# Connector_0.net
KiCad netlist of a schematic drawn in Altium Designer
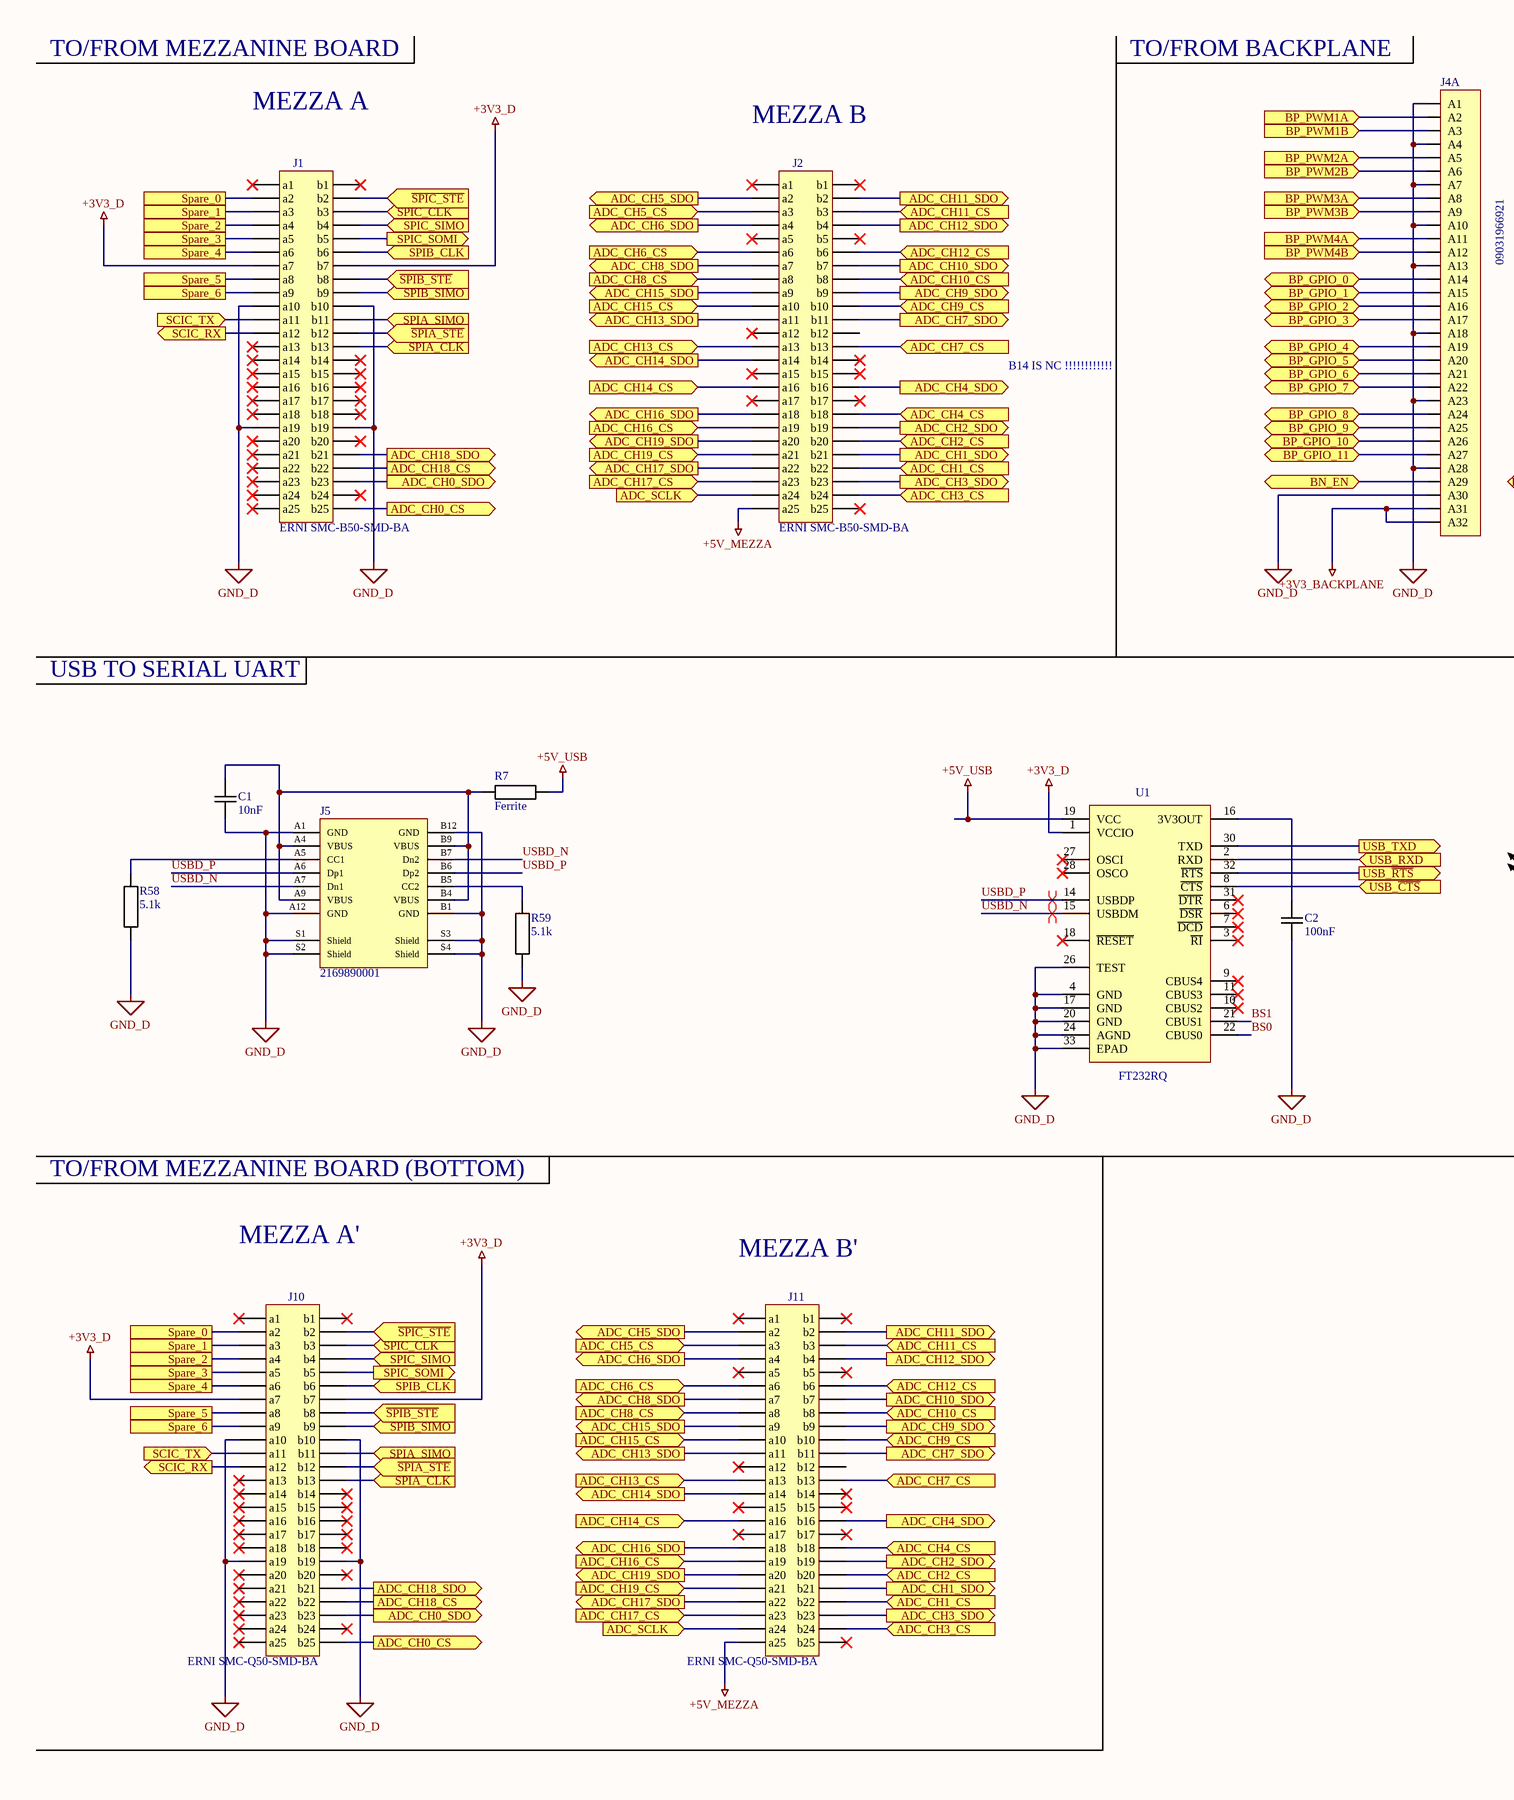
[diagram p0: Connector_0.SchDoc, left]
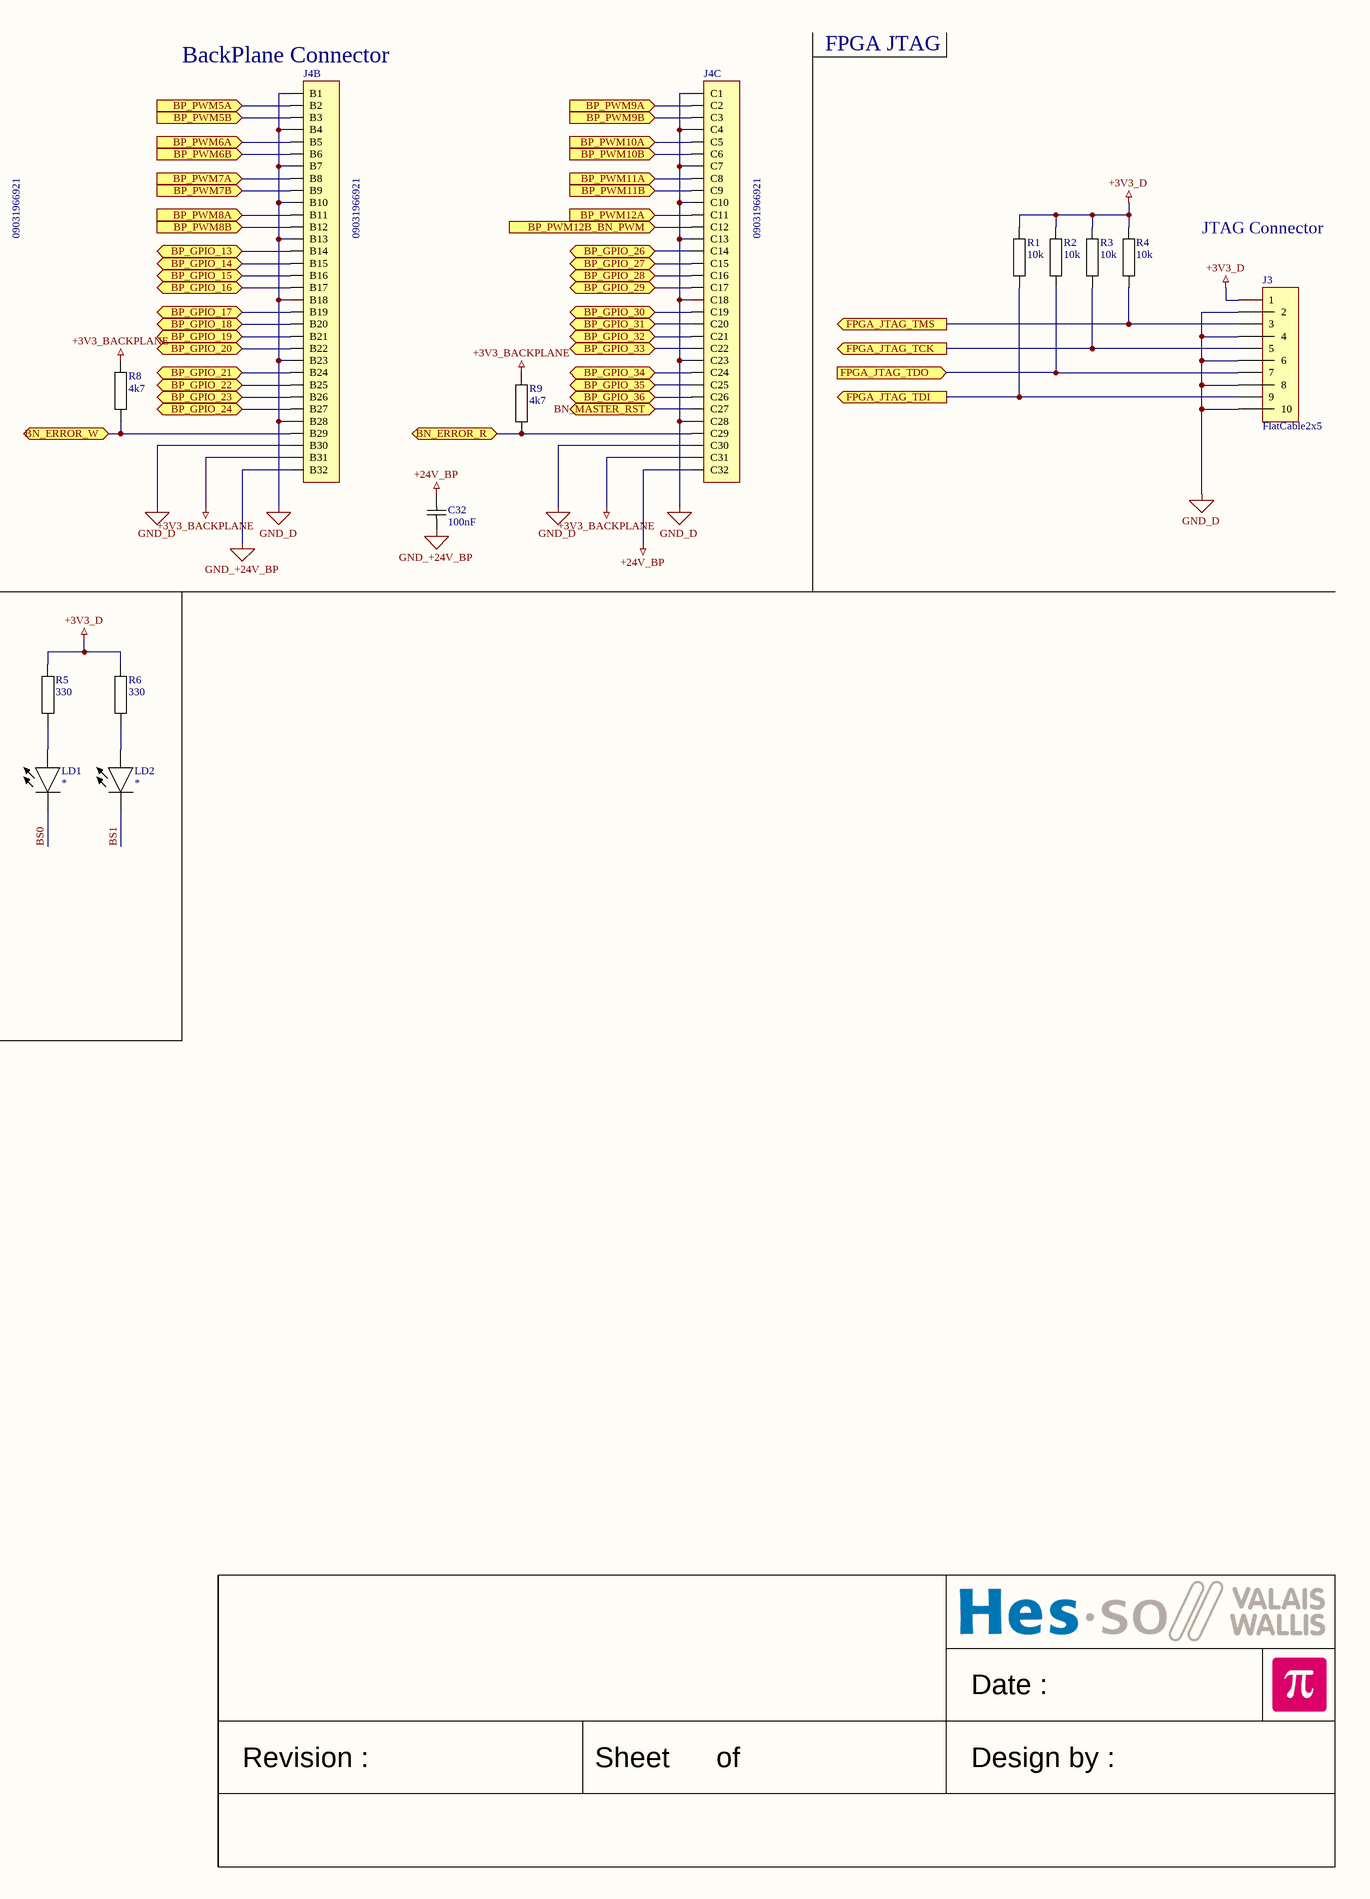
[diagram p1: Connector_0.SchDoc, right]

(export (version "E")
  (design (tool "Eeschema 10.0.6"))
  (components
    (comp (ref "C1")
      (value "10nF")
      (footprint "CAPACITOR 1608 REFLOW")
      (description "Capacitor X7R 10% 50V 1608(0603)")
      (libsource (lib "Capacitor") (part "Capacitor"))
    )
    (comp (ref "C2")
      (value "100nF")
      (footprint "CAPACITOR 1608 REFLOW")
      (description "Capacitor X7R 10% 50V 1608(0603)")
      (libsource (lib "Capacitor") (part "Capacitor"))
    )
    (comp (ref "C32")
      (value "100nF")
      (footprint "CAPACITOR 1608 REFLOW")
      (description "Capacitor X7R 10% 50V 1608(0603)")
      (libsource (lib "Capacitor") (part "Capacitor"))
    )
    (comp (ref "J1")
      (value "ERNI SMC-B50-SMD-BA")
      (footprint "ERNI SMC-B50-SMD-BA")
      (description "Female 1.27 pitch 2x25 pin connector")
      (libsource (lib "Connector") (part "ERNI SMC-B50-SMD-BA"))
    )
    (comp (ref "J2")
      (value "ERNI SMC-B50-SMD-BA")
      (footprint "ERNI SMC-B50-SMD-BA")
      (description "Female 1.27 pitch 2x25 pin connector")
      (libsource (lib "Connector") (part "ERNI SMC-B50-SMD-BA"))
    )
    (comp (ref "J3")
      (value "FlatCable2x5")
      (footprint "FlatCable2x5 2MM Right Angle TH FCI 98614-G61-10ULF")
      (libsource (lib "Connector") (part "FlatCable2x5"))
    )
    (comp (ref "J4")
      (value "09031966921")
      (footprint "DIN41612 MALE 3X32 ABC R90")
      (description "DIN41612 MALE 3X32 ABC R90")
      (fields (field (name "MANUFACTURER") "Harting"))
      (libsource (lib "Connector") (part "DIN41612 MALE 3X32 ABC R90"))
    )
    (comp (ref "J5")
      (value "2169890001")
      (footprint "USB-C-TH MOLEX 2169890001")
      (description "USB-C Receptacle Connector 24 Position Through Hole, Right Angle")
      (libsource (lib "Connector") (part "USB-C-Molex 2169890001"))
    )
    (comp (ref "J10")
      (value "ERNI SMC-Q50-SMD-BA")
      (footprint "ERNI SMC-Q50-SMD-BA")
      (description "Male 1.27 pitch 2x25 pin connector")
      (libsource (lib "Connector") (part "ERNI SMC-Q50-SMD-BA"))
    )
    (comp (ref "J11")
      (value "ERNI SMC-Q50-SMD-BA")
      (footprint "ERNI SMC-Q50-SMD-BA")
      (description "Male 1.27 pitch 2x25 pin connector")
      (libsource (lib "Connector") (part "ERNI SMC-Q50-SMD-BA"))
    )
    (comp (ref "LD1")
      (value "*")
      (footprint "LED 1608 REFLOW")
      (description "LED generic")
      (libsource (lib "Diode") (part "LED"))
    )
    (comp (ref "LD2")
      (value "*")
      (footprint "LED 1608 REFLOW")
      (description "LED generic")
      (libsource (lib "Diode") (part "LED"))
    )
    (comp (ref "R1")
      (value "10k")
      (footprint "RESISTOR 1608 REFLOW")
      (description "Resistor 1% 50V 100mW 1608(0603)")
      (libsource (lib "Resistor") (part "Resistor"))
    )
    (comp (ref "R2")
      (value "10k")
      (footprint "RESISTOR 1608 REFLOW")
      (description "Resistor 1% 50V 100mW 1608(0603)")
      (libsource (lib "Resistor") (part "Resistor"))
    )
    (comp (ref "R3")
      (value "10k")
      (footprint "RESISTOR 1608 REFLOW")
      (description "Resistor 1% 50V 100mW 1608(0603)")
      (libsource (lib "Resistor") (part "Resistor"))
    )
    (comp (ref "R4")
      (value "10k")
      (footprint "RESISTOR 1608 REFLOW")
      (description "Resistor 1% 50V 100mW 1608(0603)")
      (libsource (lib "Resistor") (part "Resistor"))
    )
    (comp (ref "R5")
      (value "330")
      (footprint "RESISTOR 2012 REFLOW")
      (description "Resistor 1% 50V 125mW 2012(0805)")
      (libsource (lib "Resistor") (part "Resistor"))
    )
    (comp (ref "R6")
      (value "330")
      (footprint "RESISTOR 2012 REFLOW")
      (description "Resistor 1% 50V 125mW 2012(0805)")
      (libsource (lib "Resistor") (part "Resistor"))
    )
    (comp (ref "R7")
      (value "Ferrite")
      (footprint "RESISTOR 1608 REFLOW")
      (description "Resistor 1% 50V 100mW 1608(0603)")
      (libsource (lib "Resistor") (part "Resistor"))
    )
    (comp (ref "R8")
      (value "4k7")
      (footprint "RESISTOR 1608 REFLOW")
      (description "Resistor 1% 50V 100mW 1608(0603)")
      (libsource (lib "Resistor") (part "Resistor"))
    )
    (comp (ref "R9")
      (value "4k7")
      (footprint "RESISTOR 1608 REFLOW")
      (description "Resistor 1% 50V 100mW 1608(0603)")
      (libsource (lib "Resistor") (part "Resistor"))
    )
    (comp (ref "R58")
      (value "5.1k")
      (footprint "RESISTOR 1608 REFLOW")
      (description "Resistor 1% 50V 100mW 1608(0603)")
      (libsource (lib "Resistor") (part "Resistor"))
    )
    (comp (ref "R59")
      (value "5.1k")
      (footprint "RESISTOR 1608 REFLOW")
      (description "Resistor 1% 50V 100mW 1608(0603)")
      (libsource (lib "Resistor") (part "Resistor"))
    )
    (comp (ref "U1")
      (value "FT232RQ")
      (footprint "QFN32 P0.5 T3.2x3.2 C5.0X5.0 H1.0")
      (description "24-Bit ADC with Ultra Low Noise PGIA - Crystal")
      (libsource (lib "IntegratedCircuit - Copy") (part "FT232RQ"))
    )
  )
  (nets
    (net (code "1") (name "+3V3_BACKPLANE") (class "Default")
      (node (ref "J4") (pin "A31") (pinfunction "A31_A31") (pintype "passive"))
      (node (ref "J4") (pin "A32") (pinfunction "A32_A32") (pintype "passive"))
      (node (ref "J4") (pin "B31") (pinfunction "B31_B31") (pintype "passive"))
      (node (ref "J4") (pin "C31") (pinfunction "C31_C31") (pintype "passive"))
      (node (ref "R8") (pin "2") (pinfunction "2_2") (pintype "passive"))
      (node (ref "R9") (pin "2") (pinfunction "2_2") (pintype "passive"))
    )
    (net (code "2") (name "+3V3_D") (class "Default")
      (node (ref "J1") (pin "a7") (pinfunction "a7_a7") (pintype "passive"))
      (node (ref "J1") (pin "b7") (pinfunction "b7_b7") (pintype "passive"))
      (node (ref "J10") (pin "a7") (pinfunction "a7_a7") (pintype "passive"))
      (node (ref "J10") (pin "b7") (pinfunction "b7_b7") (pintype "passive"))
      (node (ref "J3") (pin "1") (pinfunction "1_1") (pintype "passive"))
      (node (ref "R1") (pin "2") (pinfunction "2_2") (pintype "passive"))
      (node (ref "R2") (pin "2") (pinfunction "2_2") (pintype "passive"))
      (node (ref "R3") (pin "2") (pinfunction "2_2") (pintype "passive"))
      (node (ref "R4") (pin "2") (pinfunction "2_2") (pintype "passive"))
      (node (ref "R5") (pin "2") (pinfunction "2_2") (pintype "passive"))
      (node (ref "R6") (pin "2") (pinfunction "2_2") (pintype "passive"))
      (node (ref "U1") (pin "1") (pinfunction "VCCIO_1") (pintype "passive"))
    )
    (net (code "3") (name "+5V_MEZZA") (class "Default")
      (node (ref "J11") (pin "a25") (pinfunction "a25_a25") (pintype "passive"))
      (node (ref "J2") (pin "a25") (pinfunction "a25_a25") (pintype "passive"))
    )
    (net (code "4") (name "+5V_USB") (class "Default")
      (node (ref "R7") (pin "2") (pinfunction "2_2") (pintype "passive"))
      (node (ref "U1") (pin "19") (pinfunction "VCC_19") (pintype "passive"))
    )
    (net (code "5") (name "+24V_BP") (class "Default")
      (node (ref "C32") (pin "2") (pinfunction "2_2") (pintype "passive"))
      (node (ref "J4") (pin "C32") (pinfunction "C32_C32") (pintype "passive"))
    )
    (net (code "6") (name "/ADC_CH0_CS") (class "Default")
      (node (ref "J1") (pin "b25") (pinfunction "b25_b25") (pintype "passive"))
      (node (ref "J10") (pin "b25") (pinfunction "b25_b25") (pintype "passive"))
    )
    (net (code "7") (name "/ADC_CH0_SDO") (class "Default")
      (node (ref "J1") (pin "b23") (pinfunction "b23_b23") (pintype "passive"))
      (node (ref "J10") (pin "b23") (pinfunction "b23_b23") (pintype "passive"))
    )
    (net (code "8") (name "/ADC_CH1_CS") (class "Default")
      (node (ref "J11") (pin "b22") (pinfunction "b22_b22") (pintype "passive"))
      (node (ref "J2") (pin "b22") (pinfunction "b22_b22") (pintype "passive"))
    )
    (net (code "9") (name "/ADC_CH1_SDO") (class "Default")
      (node (ref "J11") (pin "b21") (pinfunction "b21_b21") (pintype "passive"))
      (node (ref "J2") (pin "b21") (pinfunction "b21_b21") (pintype "passive"))
    )
    (net (code "10") (name "/ADC_CH2_CS") (class "Default")
      (node (ref "J11") (pin "b20") (pinfunction "b20_b20") (pintype "passive"))
      (node (ref "J2") (pin "b20") (pinfunction "b20_b20") (pintype "passive"))
    )
    (net (code "11") (name "/ADC_CH2_SDO") (class "Default")
      (node (ref "J11") (pin "b19") (pinfunction "b19_b19") (pintype "passive"))
      (node (ref "J2") (pin "b19") (pinfunction "b19_b19") (pintype "passive"))
    )
    (net (code "12") (name "/ADC_CH3_CS") (class "Default")
      (node (ref "J11") (pin "b24") (pinfunction "b24_b24") (pintype "passive"))
      (node (ref "J2") (pin "b24") (pinfunction "b24_b24") (pintype "passive"))
    )
    (net (code "13") (name "/ADC_CH3_SDO") (class "Default")
      (node (ref "J11") (pin "b23") (pinfunction "b23_b23") (pintype "passive"))
      (node (ref "J2") (pin "b23") (pinfunction "b23_b23") (pintype "passive"))
    )
    (net (code "14") (name "/ADC_CH4_CS") (class "Default")
      (node (ref "J11") (pin "b18") (pinfunction "b18_b18") (pintype "passive"))
      (node (ref "J2") (pin "b18") (pinfunction "b18_b18") (pintype "passive"))
    )
    (net (code "15") (name "/ADC_CH4_SDO") (class "Default")
      (node (ref "J11") (pin "b16") (pinfunction "b16_b16") (pintype "passive"))
      (node (ref "J2") (pin "b16") (pinfunction "b16_b16") (pintype "passive"))
    )
    (net (code "16") (name "/ADC_CH5_CS") (class "Default")
      (node (ref "J11") (pin "a3") (pinfunction "a3_a3") (pintype "passive"))
      (node (ref "J2") (pin "a3") (pinfunction "a3_a3") (pintype "passive"))
    )
    (net (code "17") (name "/ADC_CH5_SDO") (class "Default")
      (node (ref "J11") (pin "a2") (pinfunction "a2_a2") (pintype "passive"))
      (node (ref "J2") (pin "a2") (pinfunction "a2_a2") (pintype "passive"))
    )
    (net (code "18") (name "/ADC_CH6_CS") (class "Default")
      (node (ref "J11") (pin "a6") (pinfunction "a6_a6") (pintype "passive"))
      (node (ref "J2") (pin "a6") (pinfunction "a6_a6") (pintype "passive"))
    )
    (net (code "19") (name "/ADC_CH6_SDO") (class "Default")
      (node (ref "J11") (pin "a4") (pinfunction "a4_a4") (pintype "passive"))
      (node (ref "J2") (pin "a4") (pinfunction "a4_a4") (pintype "passive"))
    )
    (net (code "20") (name "/ADC_CH7_CS") (class "Default")
      (node (ref "J11") (pin "b13") (pinfunction "b13_b13") (pintype "passive"))
      (node (ref "J2") (pin "b13") (pinfunction "b13_b13") (pintype "passive"))
    )
    (net (code "21") (name "/ADC_CH7_SDO") (class "Default")
      (node (ref "J11") (pin "b11") (pinfunction "b11_b11") (pintype "passive"))
      (node (ref "J2") (pin "b11") (pinfunction "b11_b11") (pintype "passive"))
    )
    (net (code "22") (name "/ADC_CH8_CS") (class "Default")
      (node (ref "J11") (pin "a8") (pinfunction "a8_a8") (pintype "passive"))
      (node (ref "J2") (pin "a8") (pinfunction "a8_a8") (pintype "passive"))
    )
    (net (code "23") (name "/ADC_CH8_SDO") (class "Default")
      (node (ref "J11") (pin "a7") (pinfunction "a7_a7") (pintype "passive"))
      (node (ref "J2") (pin "a7") (pinfunction "a7_a7") (pintype "passive"))
    )
    (net (code "24") (name "/ADC_CH9_CS") (class "Default")
      (node (ref "J11") (pin "b10") (pinfunction "b10_b10") (pintype "passive"))
      (node (ref "J2") (pin "b10") (pinfunction "b10_b10") (pintype "passive"))
    )
    (net (code "25") (name "/ADC_CH9_SDO") (class "Default")
      (node (ref "J11") (pin "b9") (pinfunction "b9_b9") (pintype "passive"))
      (node (ref "J2") (pin "b9") (pinfunction "b9_b9") (pintype "passive"))
    )
    (net (code "26") (name "/ADC_CH10_CS") (class "Default")
      (node (ref "J11") (pin "b8") (pinfunction "b8_b8") (pintype "passive"))
      (node (ref "J2") (pin "b8") (pinfunction "b8_b8") (pintype "passive"))
    )
    (net (code "27") (name "/ADC_CH10_SDO") (class "Default")
      (node (ref "J11") (pin "b7") (pinfunction "b7_b7") (pintype "passive"))
      (node (ref "J2") (pin "b7") (pinfunction "b7_b7") (pintype "passive"))
    )
    (net (code "28") (name "/ADC_CH11_CS") (class "Default")
      (node (ref "J11") (pin "b3") (pinfunction "b3_b3") (pintype "passive"))
      (node (ref "J2") (pin "b3") (pinfunction "b3_b3") (pintype "passive"))
    )
    (net (code "29") (name "/ADC_CH11_SDO") (class "Default")
      (node (ref "J11") (pin "b2") (pinfunction "b2_b2") (pintype "passive"))
      (node (ref "J2") (pin "b2") (pinfunction "b2_b2") (pintype "passive"))
    )
    (net (code "30") (name "/ADC_CH12_CS") (class "Default")
      (node (ref "J11") (pin "b6") (pinfunction "b6_b6") (pintype "passive"))
      (node (ref "J2") (pin "b6") (pinfunction "b6_b6") (pintype "passive"))
    )
    (net (code "31") (name "/ADC_CH12_SDO") (class "Default")
      (node (ref "J11") (pin "b4") (pinfunction "b4_b4") (pintype "passive"))
      (node (ref "J2") (pin "b4") (pinfunction "b4_b4") (pintype "passive"))
    )
    (net (code "32") (name "/ADC_CH13_CS") (class "Default")
      (node (ref "J11") (pin "a13") (pinfunction "a13_a13") (pintype "passive"))
      (node (ref "J2") (pin "a13") (pinfunction "a13_a13") (pintype "passive"))
    )
    (net (code "33") (name "/ADC_CH13_SDO") (class "Default")
      (node (ref "J11") (pin "a11") (pinfunction "a11_a11") (pintype "passive"))
      (node (ref "J2") (pin "a11") (pinfunction "a11_a11") (pintype "passive"))
    )
    (net (code "34") (name "/ADC_CH14_CS") (class "Default")
      (node (ref "J11") (pin "a16") (pinfunction "a16_a16") (pintype "passive"))
      (node (ref "J2") (pin "a16") (pinfunction "a16_a16") (pintype "passive"))
    )
    (net (code "35") (name "/ADC_CH14_SDO") (class "Default")
      (node (ref "J11") (pin "a14") (pinfunction "a14_a14") (pintype "passive"))
      (node (ref "J2") (pin "a14") (pinfunction "a14_a14") (pintype "passive"))
    )
    (net (code "36") (name "/ADC_CH15_CS") (class "Default")
      (node (ref "J11") (pin "a10") (pinfunction "a10_a10") (pintype "passive"))
      (node (ref "J2") (pin "a10") (pinfunction "a10_a10") (pintype "passive"))
    )
    (net (code "37") (name "/ADC_CH15_SDO") (class "Default")
      (node (ref "J11") (pin "a9") (pinfunction "a9_a9") (pintype "passive"))
      (node (ref "J2") (pin "a9") (pinfunction "a9_a9") (pintype "passive"))
    )
    (net (code "38") (name "/ADC_CH16_CS") (class "Default")
      (node (ref "J11") (pin "a19") (pinfunction "a19_a19") (pintype "passive"))
      (node (ref "J2") (pin "a19") (pinfunction "a19_a19") (pintype "passive"))
    )
    (net (code "39") (name "/ADC_CH16_SDO") (class "Default")
      (node (ref "J11") (pin "a18") (pinfunction "a18_a18") (pintype "passive"))
      (node (ref "J2") (pin "a18") (pinfunction "a18_a18") (pintype "passive"))
    )
    (net (code "40") (name "/ADC_CH17_CS") (class "Default")
      (node (ref "J11") (pin "a23") (pinfunction "a23_a23") (pintype "passive"))
      (node (ref "J2") (pin "a23") (pinfunction "a23_a23") (pintype "passive"))
    )
    (net (code "41") (name "/ADC_CH17_SDO") (class "Default")
      (node (ref "J11") (pin "a22") (pinfunction "a22_a22") (pintype "passive"))
      (node (ref "J2") (pin "a22") (pinfunction "a22_a22") (pintype "passive"))
    )
    (net (code "42") (name "/ADC_CH18_CS") (class "Default")
      (node (ref "J1") (pin "b22") (pinfunction "b22_b22") (pintype "passive"))
      (node (ref "J10") (pin "b22") (pinfunction "b22_b22") (pintype "passive"))
    )
    (net (code "43") (name "/ADC_CH18_SDO") (class "Default")
      (node (ref "J1") (pin "b21") (pinfunction "b21_b21") (pintype "passive"))
      (node (ref "J10") (pin "b21") (pinfunction "b21_b21") (pintype "passive"))
    )
    (net (code "44") (name "/ADC_CH19_CS") (class "Default")
      (node (ref "J11") (pin "a21") (pinfunction "a21_a21") (pintype "passive"))
      (node (ref "J2") (pin "a21") (pinfunction "a21_a21") (pintype "passive"))
    )
    (net (code "45") (name "/ADC_CH19_SDO") (class "Default")
      (node (ref "J11") (pin "a20") (pinfunction "a20_a20") (pintype "passive"))
      (node (ref "J2") (pin "a20") (pinfunction "a20_a20") (pintype "passive"))
    )
    (net (code "46") (name "/ADC_SCLK") (class "Default")
      (node (ref "J11") (pin "a24") (pinfunction "a24_a24") (pintype "passive"))
      (node (ref "J2") (pin "a24") (pinfunction "a24_a24") (pintype "passive"))
    )
    (net (code "47") (name "/BN_EN") (class "Default")
      (node (ref "J4") (pin "A29") (pinfunction "A29_A29") (pintype "passive"))
    )
    (net (code "48") (name "/BN_ERROR_R") (class "Default")
      (node (ref "J4") (pin "C29") (pinfunction "C29_C29") (pintype "passive"))
      (node (ref "R9") (pin "1") (pinfunction "1_1") (pintype "passive"))
    )
    (net (code "49") (name "/BN_ERROR_W") (class "Default")
      (node (ref "J4") (pin "B29") (pinfunction "B29_B29") (pintype "passive"))
      (node (ref "R8") (pin "1") (pinfunction "1_1") (pintype "passive"))
    )
    (net (code "50") (name "/BN_MASTER_RST") (class "Default")
      (node (ref "J4") (pin "C27") (pinfunction "C27_C27") (pintype "passive"))
    )
    (net (code "51") (name "/BP_GPIO_0") (class "Default")
      (node (ref "J4") (pin "A14") (pinfunction "A14_A14") (pintype "passive"))
    )
    (net (code "52") (name "/BP_GPIO_1") (class "Default")
      (node (ref "J4") (pin "A15") (pinfunction "A15_A15") (pintype "passive"))
    )
    (net (code "53") (name "/BP_GPIO_2") (class "Default")
      (node (ref "J4") (pin "A16") (pinfunction "A16_A16") (pintype "passive"))
    )
    (net (code "54") (name "/BP_GPIO_3") (class "Default")
      (node (ref "J4") (pin "A17") (pinfunction "A17_A17") (pintype "passive"))
    )
    (net (code "55") (name "/BP_GPIO_4") (class "Default")
      (node (ref "J4") (pin "A19") (pinfunction "A19_A19") (pintype "passive"))
    )
    (net (code "56") (name "/BP_GPIO_5") (class "Default")
      (node (ref "J4") (pin "A20") (pinfunction "A20_A20") (pintype "passive"))
    )
    (net (code "57") (name "/BP_GPIO_6") (class "Default")
      (node (ref "J4") (pin "A21") (pinfunction "A21_A21") (pintype "passive"))
    )
    (net (code "58") (name "/BP_GPIO_7") (class "Default")
      (node (ref "J4") (pin "A22") (pinfunction "A22_A22") (pintype "passive"))
    )
    (net (code "59") (name "/BP_GPIO_8") (class "Default")
      (node (ref "J4") (pin "A24") (pinfunction "A24_A24") (pintype "passive"))
    )
    (net (code "60") (name "/BP_GPIO_9") (class "Default")
      (node (ref "J4") (pin "A25") (pinfunction "A25_A25") (pintype "passive"))
    )
    (net (code "61") (name "/BP_GPIO_10") (class "Default")
      (node (ref "J4") (pin "A26") (pinfunction "A26_A26") (pintype "passive"))
    )
    (net (code "62") (name "/BP_GPIO_11") (class "Default")
      (node (ref "J4") (pin "A27") (pinfunction "A27_A27") (pintype "passive"))
    )
    (net (code "63") (name "/BP_GPIO_13") (class "Default")
      (node (ref "J4") (pin "B14") (pinfunction "B14_B14") (pintype "passive"))
    )
    (net (code "64") (name "/BP_GPIO_14") (class "Default")
      (node (ref "J4") (pin "B15") (pinfunction "B15_B15") (pintype "passive"))
    )
    (net (code "65") (name "/BP_GPIO_15") (class "Default")
      (node (ref "J4") (pin "B16") (pinfunction "B16_B16") (pintype "passive"))
    )
    (net (code "66") (name "/BP_GPIO_16") (class "Default")
      (node (ref "J4") (pin "B17") (pinfunction "B17_B17") (pintype "passive"))
    )
    (net (code "67") (name "/BP_GPIO_17") (class "Default")
      (node (ref "J4") (pin "B19") (pinfunction "B19_B19") (pintype "passive"))
    )
    (net (code "68") (name "/BP_GPIO_18") (class "Default")
      (node (ref "J4") (pin "B20") (pinfunction "B20_B20") (pintype "passive"))
    )
    (net (code "69") (name "/BP_GPIO_19") (class "Default")
      (node (ref "J4") (pin "B21") (pinfunction "B21_B21") (pintype "passive"))
    )
    (net (code "70") (name "/BP_GPIO_20") (class "Default")
      (node (ref "J4") (pin "B22") (pinfunction "B22_B22") (pintype "passive"))
    )
    (net (code "71") (name "/BP_GPIO_21") (class "Default")
      (node (ref "J4") (pin "B24") (pinfunction "B24_B24") (pintype "passive"))
    )
    (net (code "72") (name "/BP_GPIO_22") (class "Default")
      (node (ref "J4") (pin "B25") (pinfunction "B25_B25") (pintype "passive"))
    )
    (net (code "73") (name "/BP_GPIO_23") (class "Default")
      (node (ref "J4") (pin "B26") (pinfunction "B26_B26") (pintype "passive"))
    )
    (net (code "74") (name "/BP_GPIO_24") (class "Default")
      (node (ref "J4") (pin "B27") (pinfunction "B27_B27") (pintype "passive"))
    )
    (net (code "75") (name "/BP_GPIO_26") (class "Default")
      (node (ref "J4") (pin "C14") (pinfunction "C14_C14") (pintype "passive"))
    )
    (net (code "76") (name "/BP_GPIO_27") (class "Default")
      (node (ref "J4") (pin "C15") (pinfunction "C15_C15") (pintype "passive"))
    )
    (net (code "77") (name "/BP_GPIO_28") (class "Default")
      (node (ref "J4") (pin "C16") (pinfunction "C16_C16") (pintype "passive"))
    )
    (net (code "78") (name "/BP_GPIO_29") (class "Default")
      (node (ref "J4") (pin "C17") (pinfunction "C17_C17") (pintype "passive"))
    )
    (net (code "79") (name "/BP_GPIO_30") (class "Default")
      (node (ref "J4") (pin "C19") (pinfunction "C19_C19") (pintype "passive"))
    )
    (net (code "80") (name "/BP_GPIO_31") (class "Default")
      (node (ref "J4") (pin "C20") (pinfunction "C20_C20") (pintype "passive"))
    )
    (net (code "81") (name "/BP_GPIO_32") (class "Default")
      (node (ref "J4") (pin "C21") (pinfunction "C21_C21") (pintype "passive"))
    )
    (net (code "82") (name "/BP_GPIO_33") (class "Default")
      (node (ref "J4") (pin "C22") (pinfunction "C22_C22") (pintype "passive"))
    )
    (net (code "83") (name "/BP_GPIO_34") (class "Default")
      (node (ref "J4") (pin "C24") (pinfunction "C24_C24") (pintype "passive"))
    )
    (net (code "84") (name "/BP_GPIO_35") (class "Default")
      (node (ref "J4") (pin "C25") (pinfunction "C25_C25") (pintype "passive"))
    )
    (net (code "85") (name "/BP_GPIO_36") (class "Default")
      (node (ref "J4") (pin "C26") (pinfunction "C26_C26") (pintype "passive"))
    )
    (net (code "86") (name "/BP_PWM1A") (class "Default")
      (node (ref "J4") (pin "A2") (pinfunction "A2_A2") (pintype "passive"))
    )
    (net (code "87") (name "/BP_PWM1B") (class "Default")
      (node (ref "J4") (pin "A3") (pinfunction "A3_A3") (pintype "passive"))
    )
    (net (code "88") (name "/BP_PWM2A") (class "Default")
      (node (ref "J4") (pin "A5") (pinfunction "A5_A5") (pintype "passive"))
    )
    (net (code "89") (name "/BP_PWM2B") (class "Default")
      (node (ref "J4") (pin "A6") (pinfunction "A6_A6") (pintype "passive"))
    )
    (net (code "90") (name "/BP_PWM3A") (class "Default")
      (node (ref "J4") (pin "A8") (pinfunction "A8_A8") (pintype "passive"))
    )
    (net (code "91") (name "/BP_PWM3B") (class "Default")
      (node (ref "J4") (pin "A9") (pinfunction "A9_A9") (pintype "passive"))
    )
    (net (code "92") (name "/BP_PWM4A") (class "Default")
      (node (ref "J4") (pin "A11") (pinfunction "A11_A11") (pintype "passive"))
    )
    (net (code "93") (name "/BP_PWM4B") (class "Default")
      (node (ref "J4") (pin "A12") (pinfunction "A12_A12") (pintype "passive"))
    )
    (net (code "94") (name "/BP_PWM5A") (class "Default")
      (node (ref "J4") (pin "B2") (pinfunction "B2_B2") (pintype "passive"))
    )
    (net (code "95") (name "/BP_PWM5B") (class "Default")
      (node (ref "J4") (pin "B3") (pinfunction "B3_B3") (pintype "passive"))
    )
    (net (code "96") (name "/BP_PWM6A") (class "Default")
      (node (ref "J4") (pin "B5") (pinfunction "B5_B5") (pintype "passive"))
    )
    (net (code "97") (name "/BP_PWM6B") (class "Default")
      (node (ref "J4") (pin "B6") (pinfunction "B6_B6") (pintype "passive"))
    )
    (net (code "98") (name "/BP_PWM7A") (class "Default")
      (node (ref "J4") (pin "B8") (pinfunction "B8_B8") (pintype "passive"))
    )
    (net (code "99") (name "/BP_PWM7B") (class "Default")
      (node (ref "J4") (pin "B9") (pinfunction "B9_B9") (pintype "passive"))
    )
    (net (code "100") (name "/BP_PWM8A") (class "Default")
      (node (ref "J4") (pin "B11") (pinfunction "B11_B11") (pintype "passive"))
    )
    (net (code "101") (name "/BP_PWM8B") (class "Default")
      (node (ref "J4") (pin "B12") (pinfunction "B12_B12") (pintype "passive"))
    )
    (net (code "102") (name "/BP_PWM9A") (class "Default")
      (node (ref "J4") (pin "C2") (pinfunction "C2_C2") (pintype "passive"))
    )
    (net (code "103") (name "/BP_PWM9B") (class "Default")
      (node (ref "J4") (pin "C3") (pinfunction "C3_C3") (pintype "passive"))
    )
    (net (code "104") (name "/BP_PWM10A") (class "Default")
      (node (ref "J4") (pin "C5") (pinfunction "C5_C5") (pintype "passive"))
    )
    (net (code "105") (name "/BP_PWM10B") (class "Default")
      (node (ref "J4") (pin "C6") (pinfunction "C6_C6") (pintype "passive"))
    )
    (net (code "106") (name "/BP_PWM11A") (class "Default")
      (node (ref "J4") (pin "C8") (pinfunction "C8_C8") (pintype "passive"))
    )
    (net (code "107") (name "/BP_PWM11B") (class "Default")
      (node (ref "J4") (pin "C9") (pinfunction "C9_C9") (pintype "passive"))
    )
    (net (code "108") (name "/BP_PWM12A") (class "Default")
      (node (ref "J4") (pin "C11") (pinfunction "C11_C11") (pintype "passive"))
    )
    (net (code "109") (name "/BP_PWM12B_BN_PWM") (class "Default")
      (node (ref "J4") (pin "C12") (pinfunction "C12_C12") (pintype "passive"))
    )
    (net (code "110") (name "/BS0") (class "Default")
      (node (ref "LD1") (pin "1") (pinfunction "C_1") (pintype "passive"))
      (node (ref "U1") (pin "22") (pinfunction "CBUS0_22") (pintype "passive"))
    )
    (net (code "111") (name "/BS1") (class "Default")
      (node (ref "LD2") (pin "1") (pinfunction "C_1") (pintype "passive"))
      (node (ref "U1") (pin "21") (pinfunction "CBUS1_21") (pintype "passive"))
    )
    (net (code "112") (name "/FPGA_JTAG_TCK") (class "Default")
      (node (ref "J3") (pin "5") (pinfunction "5_5") (pintype "passive"))
      (node (ref "R3") (pin "1") (pinfunction "1_1") (pintype "passive"))
    )
    (net (code "113") (name "/FPGA_JTAG_TDI") (class "Default")
      (node (ref "J3") (pin "9") (pinfunction "9_9") (pintype "passive"))
      (node (ref "R1") (pin "1") (pinfunction "1_1") (pintype "passive"))
    )
    (net (code "114") (name "/FPGA_JTAG_TDO") (class "Default")
      (node (ref "J3") (pin "7") (pinfunction "7_7") (pintype "passive"))
      (node (ref "R2") (pin "1") (pinfunction "1_1") (pintype "passive"))
    )
    (net (code "115") (name "/FPGA_JTAG_TMS") (class "Default")
      (node (ref "J3") (pin "3") (pinfunction "3_3") (pintype "passive"))
      (node (ref "R4") (pin "1") (pinfunction "1_1") (pintype "passive"))
    )
    (net (code "116") (name "/SCIC_RX") (class "Default")
      (node (ref "J1") (pin "a12") (pinfunction "a12_a12") (pintype "passive"))
      (node (ref "J10") (pin "a12") (pinfunction "a12_a12") (pintype "passive"))
    )
    (net (code "117") (name "/SCIC_TX") (class "Default")
      (node (ref "J1") (pin "a11") (pinfunction "a11_a11") (pintype "passive"))
      (node (ref "J10") (pin "a11") (pinfunction "a11_a11") (pintype "passive"))
    )
    (net (code "118") (name "/SPIA_CLK") (class "Default")
      (node (ref "J1") (pin "b13") (pinfunction "b13_b13") (pintype "passive"))
      (node (ref "J10") (pin "b13") (pinfunction "b13_b13") (pintype "passive"))
    )
    (net (code "119") (name "/SPIA_SIMO") (class "Default")
      (node (ref "J1") (pin "b11") (pinfunction "b11_b11") (pintype "passive"))
      (node (ref "J10") (pin "b11") (pinfunction "b11_b11") (pintype "passive"))
    )
    (net (code "120") (name "/SPIB_CLK") (class "Default")
      (node (ref "J1") (pin "b6") (pinfunction "b6_b6") (pintype "passive"))
      (node (ref "J10") (pin "b6") (pinfunction "b6_b6") (pintype "passive"))
    )
    (net (code "121") (name "/SPIB_SIMO") (class "Default")
      (node (ref "J1") (pin "b9") (pinfunction "b9_b9") (pintype "passive"))
      (node (ref "J10") (pin "b9") (pinfunction "b9_b9") (pintype "passive"))
    )
    (net (code "122") (name "/SPIC_CLK") (class "Default")
      (node (ref "J1") (pin "b3") (pinfunction "b3_b3") (pintype "passive"))
      (node (ref "J10") (pin "b3") (pinfunction "b3_b3") (pintype "passive"))
    )
    (net (code "123") (name "/SPIC_SIMO") (class "Default")
      (node (ref "J1") (pin "b4") (pinfunction "b4_b4") (pintype "passive"))
      (node (ref "J10") (pin "b4") (pinfunction "b4_b4") (pintype "passive"))
    )
    (net (code "124") (name "/SPIC_SOMI") (class "Default")
      (node (ref "J1") (pin "b5") (pinfunction "b5_b5") (pintype "passive"))
      (node (ref "J10") (pin "b5") (pinfunction "b5_b5") (pintype "passive"))
    )
    (net (code "125") (name "/Spare_0") (class "Default")
      (node (ref "J1") (pin "a2") (pinfunction "a2_a2") (pintype "passive"))
      (node (ref "J10") (pin "a2") (pinfunction "a2_a2") (pintype "passive"))
    )
    (net (code "126") (name "/Spare_1") (class "Default")
      (node (ref "J1") (pin "a3") (pinfunction "a3_a3") (pintype "passive"))
      (node (ref "J10") (pin "a3") (pinfunction "a3_a3") (pintype "passive"))
    )
    (net (code "127") (name "/Spare_2") (class "Default")
      (node (ref "J1") (pin "a4") (pinfunction "a4_a4") (pintype "passive"))
      (node (ref "J10") (pin "a4") (pinfunction "a4_a4") (pintype "passive"))
    )
    (net (code "128") (name "/Spare_3") (class "Default")
      (node (ref "J1") (pin "a5") (pinfunction "a5_a5") (pintype "passive"))
      (node (ref "J10") (pin "a5") (pinfunction "a5_a5") (pintype "passive"))
    )
    (net (code "129") (name "/Spare_4") (class "Default")
      (node (ref "J1") (pin "a6") (pinfunction "a6_a6") (pintype "passive"))
      (node (ref "J10") (pin "a6") (pinfunction "a6_a6") (pintype "passive"))
    )
    (net (code "130") (name "/Spare_5") (class "Default")
      (node (ref "J1") (pin "a8") (pinfunction "a8_a8") (pintype "passive"))
      (node (ref "J10") (pin "a8") (pinfunction "a8_a8") (pintype "passive"))
    )
    (net (code "131") (name "/Spare_6") (class "Default")
      (node (ref "J1") (pin "a9") (pinfunction "a9_a9") (pintype "passive"))
      (node (ref "J10") (pin "a9") (pinfunction "a9_a9") (pintype "passive"))
    )
    (net (code "132") (name "/USBD_N") (class "Default")
      (node (ref "J5") (pin "A7") (pinfunction "Dn1_A7") (pintype "passive"))
      (node (ref "J5") (pin "B7") (pinfunction "Dn2_B7") (pintype "passive"))
      (node (ref "U1") (pin "15") (pinfunction "USBDM_15") (pintype "passive"))
    )
    (net (code "133") (name "/USBD_P") (class "Default")
      (node (ref "J5") (pin "A6") (pinfunction "Dp1_A6") (pintype "passive"))
      (node (ref "J5") (pin "B6") (pinfunction "Dp2_B6") (pintype "passive"))
      (node (ref "U1") (pin "14") (pinfunction "USBDP_14") (pintype "passive"))
    )
    (net (code "134") (name "/USB_RXD") (class "Default")
      (node (ref "U1") (pin "2") (pinfunction "RXD_2") (pintype "passive"))
    )
    (net (code "135") (name "/USB_TXD") (class "Default")
      (node (ref "U1") (pin "30") (pinfunction "TXD_30") (pintype "passive"))
    )
    (net (code "136") (name "/USB_~{CTS}") (class "Default")
      (node (ref "U1") (pin "8") (pinfunction "~{CTS}_8") (pintype "passive"))
    )
    (net (code "137") (name "/USB_~{RTS}") (class "Default")
      (node (ref "U1") (pin "32") (pinfunction "~{RTS}_32") (pintype "passive"))
    )
    (net (code "138") (name "/~{SPIA_STE}") (class "Default")
      (node (ref "J1") (pin "b12") (pinfunction "b12_b12") (pintype "passive"))
      (node (ref "J10") (pin "b12") (pinfunction "b12_b12") (pintype "passive"))
    )
    (net (code "139") (name "/~{SPIB_STE}") (class "Default")
      (node (ref "J1") (pin "b8") (pinfunction "b8_b8") (pintype "passive"))
      (node (ref "J10") (pin "b8") (pinfunction "b8_b8") (pintype "passive"))
    )
    (net (code "140") (name "/~{SPIC_STE}") (class "Default")
      (node (ref "J1") (pin "b2") (pinfunction "b2_b2") (pintype "passive"))
      (node (ref "J10") (pin "b2") (pinfunction "b2_b2") (pintype "passive"))
    )
    (net (code "141") (name "GND_+24V_BP") (class "Default")
      (node (ref "C32") (pin "1") (pinfunction "1_1") (pintype "passive"))
      (node (ref "J4") (pin "B32") (pinfunction "B32_B32") (pintype "passive"))
    )
    (net (code "142") (name "GND_D") (class "Default")
      (node (ref "C1") (pin "1") (pinfunction "1_1") (pintype "passive"))
      (node (ref "C2") (pin "1") (pinfunction "1_1") (pintype "passive"))
      (node (ref "J1") (pin "a10") (pinfunction "a10_a10") (pintype "passive"))
      (node (ref "J1") (pin "a19") (pinfunction "a19_a19") (pintype "passive"))
      (node (ref "J1") (pin "b10") (pinfunction "b10_b10") (pintype "passive"))
      (node (ref "J1") (pin "b19") (pinfunction "b19_b19") (pintype "passive"))
      (node (ref "J10") (pin "a10") (pinfunction "a10_a10") (pintype "passive"))
      (node (ref "J10") (pin "a19") (pinfunction "a19_a19") (pintype "passive"))
      (node (ref "J10") (pin "b10") (pinfunction "b10_b10") (pintype "passive"))
      (node (ref "J10") (pin "b19") (pinfunction "b19_b19") (pintype "passive"))
      (node (ref "J3") (pin "10") (pinfunction "10_10") (pintype "passive"))
      (node (ref "J3") (pin "2") (pinfunction "2_2") (pintype "passive"))
      (node (ref "J3") (pin "4") (pinfunction "4_4") (pintype "passive"))
      (node (ref "J3") (pin "6") (pinfunction "6_6") (pintype "passive"))
      (node (ref "J3") (pin "8") (pinfunction "8_8") (pintype "passive"))
      (node (ref "J4") (pin "A1") (pinfunction "A1_A1") (pintype "passive"))
      (node (ref "J4") (pin "A10") (pinfunction "A10_A10") (pintype "passive"))
      (node (ref "J4") (pin "A13") (pinfunction "A13_A13") (pintype "passive"))
      (node (ref "J4") (pin "A18") (pinfunction "A18_A18") (pintype "passive"))
      (node (ref "J4") (pin "A23") (pinfunction "A23_A23") (pintype "passive"))
      (node (ref "J4") (pin "A28") (pinfunction "A28_A28") (pintype "passive"))
      (node (ref "J4") (pin "A30") (pinfunction "A30_A30") (pintype "passive"))
      (node (ref "J4") (pin "A4") (pinfunction "A4_A4") (pintype "passive"))
      (node (ref "J4") (pin "A7") (pinfunction "A7_A7") (pintype "passive"))
      (node (ref "J4") (pin "B1") (pinfunction "B1_B1") (pintype "passive"))
      (node (ref "J4") (pin "B10") (pinfunction "B10_B10") (pintype "passive"))
      (node (ref "J4") (pin "B13") (pinfunction "B13_B13") (pintype "passive"))
      (node (ref "J4") (pin "B18") (pinfunction "B18_B18") (pintype "passive"))
      (node (ref "J4") (pin "B23") (pinfunction "B23_B23") (pintype "passive"))
      (node (ref "J4") (pin "B28") (pinfunction "B28_B28") (pintype "passive"))
      (node (ref "J4") (pin "B30") (pinfunction "B30_B30") (pintype "passive"))
      (node (ref "J4") (pin "B4") (pinfunction "B4_B4") (pintype "passive"))
      (node (ref "J4") (pin "B7") (pinfunction "B7_B7") (pintype "passive"))
      (node (ref "J4") (pin "C1") (pinfunction "C1_C1") (pintype "passive"))
      (node (ref "J4") (pin "C10") (pinfunction "C10_C10") (pintype "passive"))
      (node (ref "J4") (pin "C13") (pinfunction "C13_C13") (pintype "passive"))
      (node (ref "J4") (pin "C18") (pinfunction "C18_C18") (pintype "passive"))
      (node (ref "J4") (pin "C23") (pinfunction "C23_C23") (pintype "passive"))
      (node (ref "J4") (pin "C28") (pinfunction "C28_C28") (pintype "passive"))
      (node (ref "J4") (pin "C30") (pinfunction "C30_C30") (pintype "passive"))
      (node (ref "J4") (pin "C4") (pinfunction "C4_C4") (pintype "passive"))
      (node (ref "J4") (pin "C7") (pinfunction "C7_C7") (pintype "passive"))
      (node (ref "J5") (pin "A1") (pinfunction "GND_A1") (pintype "passive"))
      (node (ref "J5") (pin "A12") (pinfunction "GND_A12") (pintype "passive"))
      (node (ref "J5") (pin "B1") (pinfunction "GND_B1") (pintype "passive"))
      (node (ref "J5") (pin "B12") (pinfunction "GND_B12") (pintype "passive"))
      (node (ref "J5") (pin "S1") (pinfunction "Shield_S1") (pintype "passive"))
      (node (ref "J5") (pin "S2") (pinfunction "Shield_S2") (pintype "passive"))
      (node (ref "J5") (pin "S3") (pinfunction "Shield_S3") (pintype "passive"))
      (node (ref "J5") (pin "S4") (pinfunction "Shield_S4") (pintype "passive"))
      (node (ref "R58") (pin "2") (pinfunction "2_2") (pintype "passive"))
      (node (ref "R59") (pin "2") (pinfunction "2_2") (pintype "passive"))
      (node (ref "U1") (pin "17") (pinfunction "GND_17") (pintype "passive"))
      (node (ref "U1") (pin "20") (pinfunction "GND_20") (pintype "passive"))
      (node (ref "U1") (pin "24") (pinfunction "AGND_24") (pintype "passive"))
      (node (ref "U1") (pin "26") (pinfunction "TEST_26") (pintype "passive"))
      (node (ref "U1") (pin "33") (pinfunction "EPAD_33") (pintype "passive"))
      (node (ref "U1") (pin "4") (pinfunction "GND_4") (pintype "passive"))
    )
    (net (code "143") (name "Net-(C1-Pad2)") (class "Default")
      (node (ref "C1") (pin "2") (pinfunction "2_2") (pintype "passive"))
      (node (ref "J5") (pin "A4") (pinfunction "VBUS_A4") (pintype "passive"))
      (node (ref "J5") (pin "A9") (pinfunction "VBUS_A9") (pintype "passive"))
      (node (ref "J5") (pin "B4") (pinfunction "VBUS_B4") (pintype "passive"))
      (node (ref "J5") (pin "B9") (pinfunction "VBUS_B9") (pintype "passive"))
      (node (ref "R7") (pin "1") (pinfunction "1_1") (pintype "passive"))
    )
    (net (code "144") (name "Net-(J5-CC1)") (class "Default")
      (node (ref "J5") (pin "A5") (pinfunction "CC1_A5") (pintype "passive"))
      (node (ref "R58") (pin "1") (pinfunction "1_1") (pintype "passive"))
    )
    (net (code "145") (name "Net-(J5-CC2)") (class "Default")
      (node (ref "J5") (pin "B5") (pinfunction "CC2_B5") (pintype "passive"))
      (node (ref "R59") (pin "1") (pinfunction "1_1") (pintype "passive"))
    )
    (net (code "146") (name "Net-(LD1-A)") (class "Default")
      (node (ref "LD1") (pin "2") (pinfunction "A_2") (pintype "passive"))
      (node (ref "R5") (pin "1") (pinfunction "1_1") (pintype "passive"))
    )
    (net (code "147") (name "Net-(LD2-A)") (class "Default")
      (node (ref "LD2") (pin "2") (pinfunction "A_2") (pintype "passive"))
      (node (ref "R6") (pin "1") (pinfunction "1_1") (pintype "passive"))
    )
    (net (code "148") (name "Net-(U1-3V3OUT)") (class "Default")
      (node (ref "C2") (pin "2") (pinfunction "2_2") (pintype "passive"))
      (node (ref "U1") (pin "16") (pinfunction "3V3OUT_16") (pintype "passive"))
    )
    (net (code "149") (name "unconnected-(J1-Pada1)") (class "Default")
      (node (ref "J1") (pin "a1") (pinfunction "a1_a1") (pintype "passive+no_connect"))
    )
    (net (code "150") (name "unconnected-(J1-Pada13)") (class "Default")
      (node (ref "J1") (pin "a13") (pinfunction "a13_a13") (pintype "passive+no_connect"))
    )
    (net (code "151") (name "unconnected-(J1-Pada14)") (class "Default")
      (node (ref "J1") (pin "a14") (pinfunction "a14_a14") (pintype "passive+no_connect"))
    )
    (net (code "152") (name "unconnected-(J1-Pada15)") (class "Default")
      (node (ref "J1") (pin "a15") (pinfunction "a15_a15") (pintype "passive+no_connect"))
    )
    (net (code "153") (name "unconnected-(J1-Pada16)") (class "Default")
      (node (ref "J1") (pin "a16") (pinfunction "a16_a16") (pintype "passive+no_connect"))
    )
    (net (code "154") (name "unconnected-(J1-Pada17)") (class "Default")
      (node (ref "J1") (pin "a17") (pinfunction "a17_a17") (pintype "passive+no_connect"))
    )
    (net (code "155") (name "unconnected-(J1-Pada18)") (class "Default")
      (node (ref "J1") (pin "a18") (pinfunction "a18_a18") (pintype "passive+no_connect"))
    )
    (net (code "156") (name "unconnected-(J1-Pada20)") (class "Default")
      (node (ref "J1") (pin "a20") (pinfunction "a20_a20") (pintype "passive+no_connect"))
    )
    (net (code "157") (name "unconnected-(J1-Pada21)") (class "Default")
      (node (ref "J1") (pin "a21") (pinfunction "a21_a21") (pintype "passive+no_connect"))
    )
    (net (code "158") (name "unconnected-(J1-Pada22)") (class "Default")
      (node (ref "J1") (pin "a22") (pinfunction "a22_a22") (pintype "passive+no_connect"))
    )
    (net (code "159") (name "unconnected-(J1-Pada23)") (class "Default")
      (node (ref "J1") (pin "a23") (pinfunction "a23_a23") (pintype "passive+no_connect"))
    )
    (net (code "160") (name "unconnected-(J1-Pada24)") (class "Default")
      (node (ref "J1") (pin "a24") (pinfunction "a24_a24") (pintype "passive+no_connect"))
    )
    (net (code "161") (name "unconnected-(J1-Pada25)") (class "Default")
      (node (ref "J1") (pin "a25") (pinfunction "a25_a25") (pintype "passive+no_connect"))
    )
    (net (code "162") (name "unconnected-(J1-Padb1)") (class "Default")
      (node (ref "J1") (pin "b1") (pinfunction "b1_b1") (pintype "passive+no_connect"))
    )
    (net (code "163") (name "unconnected-(J1-Padb14)") (class "Default")
      (node (ref "J1") (pin "b14") (pinfunction "b14_b14") (pintype "passive+no_connect"))
    )
    (net (code "164") (name "unconnected-(J1-Padb15)") (class "Default")
      (node (ref "J1") (pin "b15") (pinfunction "b15_b15") (pintype "passive+no_connect"))
    )
    (net (code "165") (name "unconnected-(J1-Padb16)") (class "Default")
      (node (ref "J1") (pin "b16") (pinfunction "b16_b16") (pintype "passive+no_connect"))
    )
    (net (code "166") (name "unconnected-(J1-Padb17)") (class "Default")
      (node (ref "J1") (pin "b17") (pinfunction "b17_b17") (pintype "passive+no_connect"))
    )
    (net (code "167") (name "unconnected-(J1-Padb18)") (class "Default")
      (node (ref "J1") (pin "b18") (pinfunction "b18_b18") (pintype "passive+no_connect"))
    )
    (net (code "168") (name "unconnected-(J1-Padb20)") (class "Default")
      (node (ref "J1") (pin "b20") (pinfunction "b20_b20") (pintype "passive+no_connect"))
    )
    (net (code "169") (name "unconnected-(J1-Padb24)") (class "Default")
      (node (ref "J1") (pin "b24") (pinfunction "b24_b24") (pintype "passive+no_connect"))
    )
    (net (code "170") (name "unconnected-(J2-Pada1)") (class "Default")
      (node (ref "J2") (pin "a1") (pinfunction "a1_a1") (pintype "passive+no_connect"))
    )
    (net (code "171") (name "unconnected-(J2-Pada5)") (class "Default")
      (node (ref "J2") (pin "a5") (pinfunction "a5_a5") (pintype "passive+no_connect"))
    )
    (net (code "172") (name "unconnected-(J2-Pada12)") (class "Default")
      (node (ref "J2") (pin "a12") (pinfunction "a12_a12") (pintype "passive+no_connect"))
    )
    (net (code "173") (name "unconnected-(J2-Pada15)") (class "Default")
      (node (ref "J2") (pin "a15") (pinfunction "a15_a15") (pintype "passive+no_connect"))
    )
    (net (code "174") (name "unconnected-(J2-Pada17)") (class "Default")
      (node (ref "J2") (pin "a17") (pinfunction "a17_a17") (pintype "passive+no_connect"))
    )
    (net (code "175") (name "unconnected-(J2-Padb1)") (class "Default")
      (node (ref "J2") (pin "b1") (pinfunction "b1_b1") (pintype "passive+no_connect"))
    )
    (net (code "176") (name "unconnected-(J2-Padb5)") (class "Default")
      (node (ref "J2") (pin "b5") (pinfunction "b5_b5") (pintype "passive+no_connect"))
    )
    (net (code "177") (name "unconnected-(J2-Padb12)") (class "Default")
      (node (ref "J2") (pin "b12") (pinfunction "b12_b12") (pintype "passive"))
    )
    (net (code "178") (name "unconnected-(J2-Padb14)") (class "Default")
      (node (ref "J2") (pin "b14") (pinfunction "b14_b14") (pintype "passive+no_connect"))
    )
    (net (code "179") (name "unconnected-(J2-Padb15)") (class "Default")
      (node (ref "J2") (pin "b15") (pinfunction "b15_b15") (pintype "passive+no_connect"))
    )
    (net (code "180") (name "unconnected-(J2-Padb17)") (class "Default")
      (node (ref "J2") (pin "b17") (pinfunction "b17_b17") (pintype "passive+no_connect"))
    )
    (net (code "181") (name "unconnected-(J2-Padb25)") (class "Default")
      (node (ref "J2") (pin "b25") (pinfunction "b25_b25") (pintype "passive+no_connect"))
    )
    (net (code "182") (name "unconnected-(J10-Pada1)") (class "Default")
      (node (ref "J10") (pin "a1") (pinfunction "a1_a1") (pintype "passive+no_connect"))
    )
    (net (code "183") (name "unconnected-(J10-Pada13)") (class "Default")
      (node (ref "J10") (pin "a13") (pinfunction "a13_a13") (pintype "passive+no_connect"))
    )
    (net (code "184") (name "unconnected-(J10-Pada14)") (class "Default")
      (node (ref "J10") (pin "a14") (pinfunction "a14_a14") (pintype "passive+no_connect"))
    )
    (net (code "185") (name "unconnected-(J10-Pada15)") (class "Default")
      (node (ref "J10") (pin "a15") (pinfunction "a15_a15") (pintype "passive+no_connect"))
    )
    (net (code "186") (name "unconnected-(J10-Pada16)") (class "Default")
      (node (ref "J10") (pin "a16") (pinfunction "a16_a16") (pintype "passive+no_connect"))
    )
    (net (code "187") (name "unconnected-(J10-Pada17)") (class "Default")
      (node (ref "J10") (pin "a17") (pinfunction "a17_a17") (pintype "passive+no_connect"))
    )
    (net (code "188") (name "unconnected-(J10-Pada18)") (class "Default")
      (node (ref "J10") (pin "a18") (pinfunction "a18_a18") (pintype "passive+no_connect"))
    )
    (net (code "189") (name "unconnected-(J10-Pada20)") (class "Default")
      (node (ref "J10") (pin "a20") (pinfunction "a20_a20") (pintype "passive+no_connect"))
    )
    (net (code "190") (name "unconnected-(J10-Pada21)") (class "Default")
      (node (ref "J10") (pin "a21") (pinfunction "a21_a21") (pintype "passive+no_connect"))
    )
    (net (code "191") (name "unconnected-(J10-Pada22)") (class "Default")
      (node (ref "J10") (pin "a22") (pinfunction "a22_a22") (pintype "passive+no_connect"))
    )
    (net (code "192") (name "unconnected-(J10-Pada23)") (class "Default")
      (node (ref "J10") (pin "a23") (pinfunction "a23_a23") (pintype "passive+no_connect"))
    )
    (net (code "193") (name "unconnected-(J10-Pada24)") (class "Default")
      (node (ref "J10") (pin "a24") (pinfunction "a24_a24") (pintype "passive+no_connect"))
    )
    (net (code "194") (name "unconnected-(J10-Pada25)") (class "Default")
      (node (ref "J10") (pin "a25") (pinfunction "a25_a25") (pintype "passive+no_connect"))
    )
    (net (code "195") (name "unconnected-(J10-Padb1)") (class "Default")
      (node (ref "J10") (pin "b1") (pinfunction "b1_b1") (pintype "passive+no_connect"))
    )
    (net (code "196") (name "unconnected-(J10-Padb14)") (class "Default")
      (node (ref "J10") (pin "b14") (pinfunction "b14_b14") (pintype "passive+no_connect"))
    )
    (net (code "197") (name "unconnected-(J10-Padb15)") (class "Default")
      (node (ref "J10") (pin "b15") (pinfunction "b15_b15") (pintype "passive+no_connect"))
    )
    (net (code "198") (name "unconnected-(J10-Padb16)") (class "Default")
      (node (ref "J10") (pin "b16") (pinfunction "b16_b16") (pintype "passive+no_connect"))
    )
    (net (code "199") (name "unconnected-(J10-Padb17)") (class "Default")
      (node (ref "J10") (pin "b17") (pinfunction "b17_b17") (pintype "passive+no_connect"))
    )
    (net (code "200") (name "unconnected-(J10-Padb18)") (class "Default")
      (node (ref "J10") (pin "b18") (pinfunction "b18_b18") (pintype "passive+no_connect"))
    )
    (net (code "201") (name "unconnected-(J10-Padb20)") (class "Default")
      (node (ref "J10") (pin "b20") (pinfunction "b20_b20") (pintype "passive+no_connect"))
    )
    (net (code "202") (name "unconnected-(J10-Padb24)") (class "Default")
      (node (ref "J10") (pin "b24") (pinfunction "b24_b24") (pintype "passive+no_connect"))
    )
    (net (code "203") (name "unconnected-(J11-Pada1)") (class "Default")
      (node (ref "J11") (pin "a1") (pinfunction "a1_a1") (pintype "passive+no_connect"))
    )
    (net (code "204") (name "unconnected-(J11-Pada5)") (class "Default")
      (node (ref "J11") (pin "a5") (pinfunction "a5_a5") (pintype "passive+no_connect"))
    )
    (net (code "205") (name "unconnected-(J11-Pada12)") (class "Default")
      (node (ref "J11") (pin "a12") (pinfunction "a12_a12") (pintype "passive+no_connect"))
    )
    (net (code "206") (name "unconnected-(J11-Pada15)") (class "Default")
      (node (ref "J11") (pin "a15") (pinfunction "a15_a15") (pintype "passive+no_connect"))
    )
    (net (code "207") (name "unconnected-(J11-Pada17)") (class "Default")
      (node (ref "J11") (pin "a17") (pinfunction "a17_a17") (pintype "passive+no_connect"))
    )
    (net (code "208") (name "unconnected-(J11-Padb1)") (class "Default")
      (node (ref "J11") (pin "b1") (pinfunction "b1_b1") (pintype "passive+no_connect"))
    )
    (net (code "209") (name "unconnected-(J11-Padb5)") (class "Default")
      (node (ref "J11") (pin "b5") (pinfunction "b5_b5") (pintype "passive+no_connect"))
    )
    (net (code "210") (name "unconnected-(J11-Padb12)") (class "Default")
      (node (ref "J11") (pin "b12") (pinfunction "b12_b12") (pintype "passive"))
    )
    (net (code "211") (name "unconnected-(J11-Padb14)") (class "Default")
      (node (ref "J11") (pin "b14") (pinfunction "b14_b14") (pintype "passive+no_connect"))
    )
    (net (code "212") (name "unconnected-(J11-Padb15)") (class "Default")
      (node (ref "J11") (pin "b15") (pinfunction "b15_b15") (pintype "passive+no_connect"))
    )
    (net (code "213") (name "unconnected-(J11-Padb17)") (class "Default")
      (node (ref "J11") (pin "b17") (pinfunction "b17_b17") (pintype "passive+no_connect"))
    )
    (net (code "214") (name "unconnected-(J11-Padb25)") (class "Default")
      (node (ref "J11") (pin "b25") (pinfunction "b25_b25") (pintype "passive+no_connect"))
    )
    (net (code "215") (name "unconnected-(U1-CBUS2-Pad10)") (class "Default")
      (node (ref "U1") (pin "10") (pinfunction "CBUS2_10") (pintype "passive+no_connect"))
    )
    (net (code "216") (name "unconnected-(U1-CBUS3-Pad11)") (class "Default")
      (node (ref "U1") (pin "11") (pinfunction "CBUS3_11") (pintype "passive+no_connect"))
    )
    (net (code "217") (name "unconnected-(U1-CBUS4-Pad9)") (class "Default")
      (node (ref "U1") (pin "9") (pinfunction "CBUS4_9") (pintype "passive+no_connect"))
    )
    (net (code "218") (name "unconnected-(U1-OSCI-Pad27)") (class "Default")
      (node (ref "U1") (pin "27") (pinfunction "OSCI_27") (pintype "passive+no_connect"))
    )
    (net (code "219") (name "unconnected-(U1-OSCO-Pad28)") (class "Default")
      (node (ref "U1") (pin "28") (pinfunction "OSCO_28") (pintype "passive+no_connect"))
    )
    (net (code "220") (name "unconnected-(U1-Pad5)") (class "Default")
      (node (ref "U1") (pin "5") (pintype "passive"))
    )
    (net (code "221") (name "unconnected-(U1-Pad12)") (class "Default")
      (node (ref "U1") (pin "12") (pintype "passive"))
    )
    (net (code "222") (name "unconnected-(U1-Pad13)") (class "Default")
      (node (ref "U1") (pin "13") (pintype "passive"))
    )
    (net (code "223") (name "unconnected-(U1-Pad23)") (class "Default")
      (node (ref "U1") (pin "23") (pintype "passive"))
    )
    (net (code "224") (name "unconnected-(U1-Pad25)") (class "Default")
      (node (ref "U1") (pin "25") (pintype "passive"))
    )
    (net (code "225") (name "unconnected-(U1-Pad29)") (class "Default")
      (node (ref "U1") (pin "29") (pintype "passive"))
    )
    (net (code "226") (name "unconnected-(U1-~{DCD}-Pad7)") (class "Default")
      (node (ref "U1") (pin "7") (pinfunction "~{DCD}_7") (pintype "passive+no_connect"))
    )
    (net (code "227") (name "unconnected-(U1-~{DSR}-Pad6)") (class "Default")
      (node (ref "U1") (pin "6") (pinfunction "~{DSR}_6") (pintype "passive+no_connect"))
    )
    (net (code "228") (name "unconnected-(U1-~{DTR}-Pad31)") (class "Default")
      (node (ref "U1") (pin "31") (pinfunction "~{DTR}_31") (pintype "passive+no_connect"))
    )
    (net (code "229") (name "unconnected-(U1-~{RESET}-Pad18)") (class "Default")
      (node (ref "U1") (pin "18") (pinfunction "~{RESET}_18") (pintype "passive+no_connect"))
    )
    (net (code "230") (name "unconnected-(U1-~{RI}-Pad3)") (class "Default")
      (node (ref "U1") (pin "3") (pinfunction "~{RI}_3") (pintype "passive+no_connect"))
    )
  )
)
